# pwr_brk.net
KiCad netlist of a schematic drawn in Altium Designer
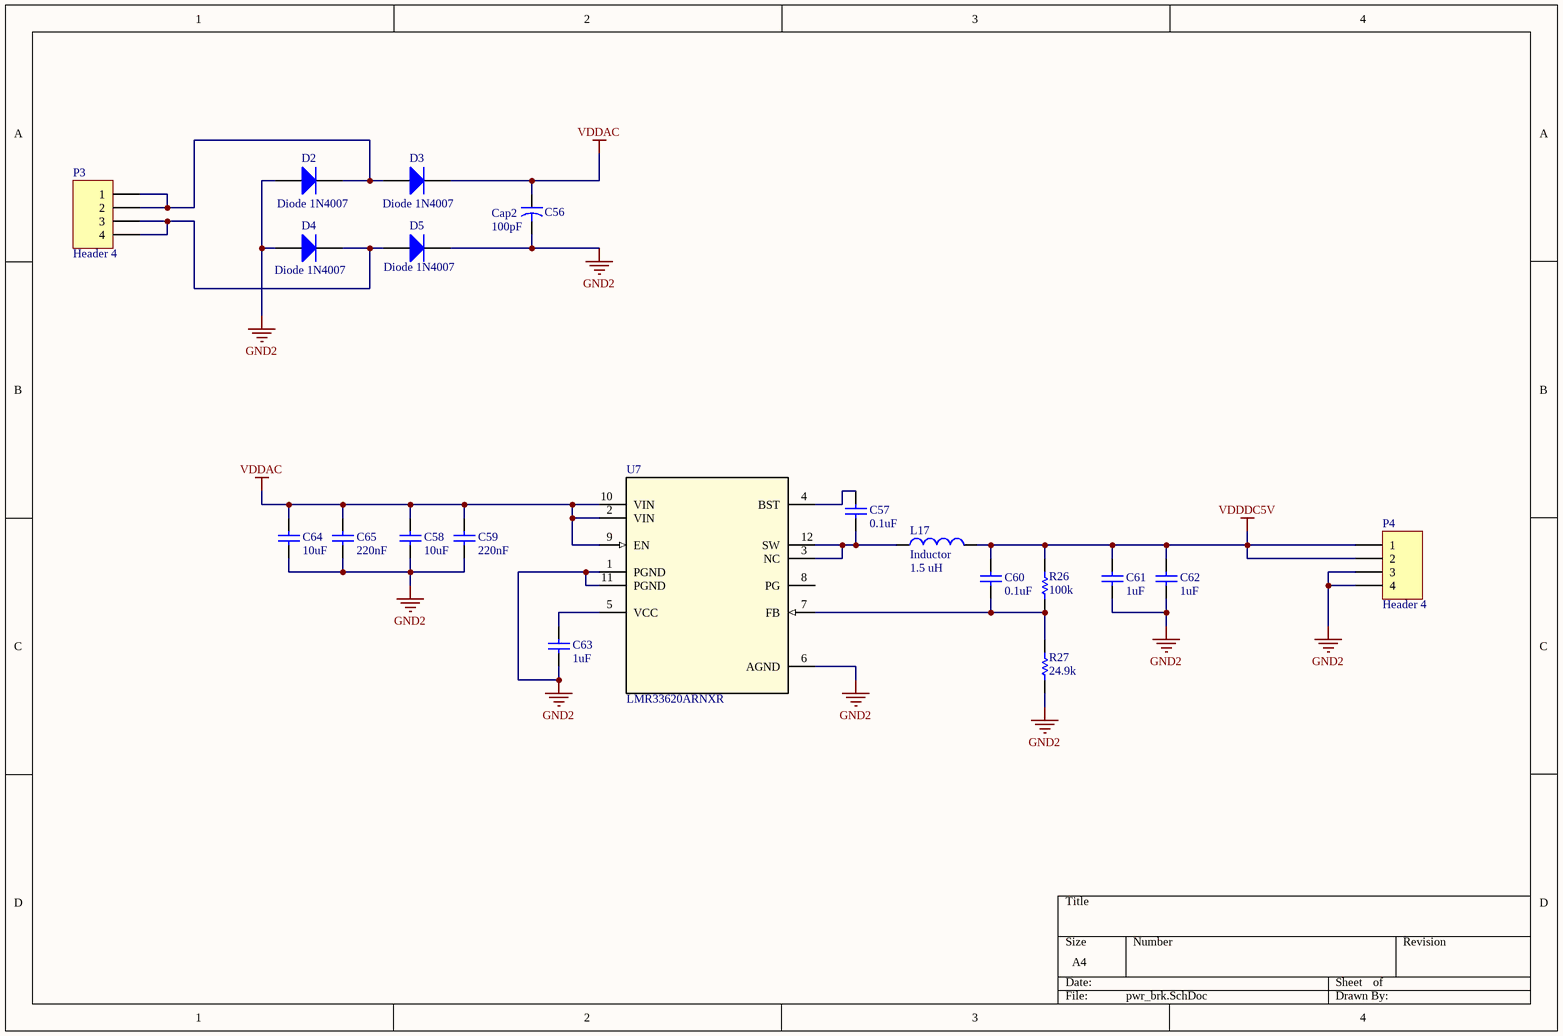
[diagram p0: pwr_brk.SchDoc]

(export (version "E")
  (design (tool "Eeschema 10.0.6"))
  (components
    (comp (ref "C56")
      (value "Cap2")
      (footprint "CAPR5-4X5")
      (description "Capacitor")
      (fields (field (name "ALTIUM_VALUE") "100pF") (field (name "PUBLISHER") "Altium Limited"))
      (libsource (lib "Miscellaneous Devices") (part "Cap2"))
    )
    (comp (ref "C57")
      (value "0.1uF")
      (footprint "C_0402")
      (libsource (lib "Miscellaneous Devices") (part "Cap"))
    )
    (comp (ref "C58")
      (value "10uF")
      (footprint "CAPC1608X05N")
      (libsource (lib "Miscellaneous Devices") (part "Cap"))
    )
    (comp (ref "C59")
      (value "220nF")
      (footprint "C_0402")
      (libsource (lib "Miscellaneous Devices") (part "Cap"))
    )
    (comp (ref "C60")
      (value "0.1uF")
      (footprint "C_0402")
      (libsource (lib "Miscellaneous Devices") (part "Cap"))
    )
    (comp (ref "C61")
      (value "1uF")
      (footprint "CAPC1608X05N")
      (libsource (lib "Miscellaneous Devices") (part "Cap"))
    )
    (comp (ref "C62")
      (value "1uF")
      (footprint "CAPC1608X05N")
      (libsource (lib "Miscellaneous Devices") (part "Cap"))
    )
    (comp (ref "C63")
      (value "1uF")
      (footprint "C_0402")
      (libsource (lib "Miscellaneous Devices") (part "Cap"))
    )
    (comp (ref "C64")
      (value "10uF")
      (footprint "CAPC1608X05N")
      (libsource (lib "Miscellaneous Devices") (part "Cap"))
    )
    (comp (ref "C65")
      (value "220nF")
      (footprint "C_0402")
      (libsource (lib "Miscellaneous Devices") (part "Cap"))
    )
    (comp (ref "D2")
      (value "Diode 1N4007")
      (footprint "DO-41")
      (description "1 Amp General Purpose Rectifier")
      (fields (field (name "PUBLISHER") "Altium Limited"))
      (libsource (lib "Miscellaneous Devices") (part "Diode 1N4007"))
    )
    (comp (ref "D3")
      (value "Diode 1N4007")
      (footprint "DO-41")
      (description "1 Amp General Purpose Rectifier")
      (fields (field (name "PUBLISHER") "Altium Limited"))
      (libsource (lib "Miscellaneous Devices") (part "Diode 1N4007"))
    )
    (comp (ref "D4")
      (value "Diode 1N4007")
      (footprint "DO-41")
      (description "1 Amp General Purpose Rectifier")
      (fields (field (name "PUBLISHER") "Altium Limited"))
      (libsource (lib "Miscellaneous Devices") (part "Diode 1N4007"))
    )
    (comp (ref "D5")
      (value "Diode 1N4007")
      (footprint "DO-41")
      (description "1 Amp General Purpose Rectifier")
      (fields (field (name "PUBLISHER") "Altium Limited"))
      (libsource (lib "Miscellaneous Devices") (part "Diode 1N4007"))
    )
    (comp (ref "L17")
      (value "Inductor")
      (footprint "INDC2016X10N")
      (fields (field (name "ALTIUM_VALUE") "1.5 uH") (field (name "PUBLISHER") "Altium Limited"))
      (libsource (lib "Miscellaneous Devices") (part "Inductor"))
    )
    (comp (ref "P3")
      (value "Header 4")
      (footprint "HDR1X4")
      (description "Header, 4-Pin")
      (fields (field (name "PUBLISHER") "Altium Limited"))
      (libsource (lib "Miscellaneous Connectors") (part "Header 4"))
    )
    (comp (ref "P4")
      (value "Header 4")
      (footprint "HDR1X4")
      (description "Header, 4-Pin")
      (fields (field (name "PUBLISHER") "Altium Limited"))
      (libsource (lib "") (part "Header 4_1"))
    )
    (comp (ref "R26")
      (value "Res1")
      (footprint "R_0402")
      (description "Resistor")
      (fields (field (name "ALTIUM_UNNAMED_1") "100k"))
      (libsource (lib "Miscellaneous Devices") (part "Res1"))
    )
    (comp (ref "R27")
      (value "Res1")
      (footprint "R_0402")
      (description "Resistor")
      (fields (field (name "ALTIUM_UNNAMED_1") "24.9k"))
      (libsource (lib "Miscellaneous Devices") (part "Res1"))
    )
    (comp (ref "U7")
      (value "LMR33620ARNXR")
      (footprint "RNX0012B")
      (description "Imported")
      (fields (field (name "MANUFACTURER") "Texas Instruments"))
      (libsource (lib "LMR33620") (part "LMR33620ARNXR"))
    )
  )
  (nets
    (net (code "1") (name "GND2") (class "Default")
      (node (ref "C56") (pin "2") (pinfunction "2_2") (pintype "passive"))
      (node (ref "C58") (pin "1") (pinfunction "1_1") (pintype "passive"))
      (node (ref "C59") (pin "1") (pinfunction "1_1") (pintype "passive"))
      (node (ref "C61") (pin "1") (pinfunction "1_1") (pintype "passive"))
      (node (ref "C62") (pin "1") (pinfunction "1_1") (pintype "passive"))
      (node (ref "C63") (pin "1") (pinfunction "1_1") (pintype "passive"))
      (node (ref "C64") (pin "1") (pinfunction "1_1") (pintype "passive"))
      (node (ref "C65") (pin "1") (pinfunction "1_1") (pintype "passive"))
      (node (ref "D2") (pin "1") (pinfunction "A_1") (pintype "passive"))
      (node (ref "D4") (pin "1") (pinfunction "A_1") (pintype "passive"))
      (node (ref "D5") (pin "2") (pinfunction "K_2") (pintype "passive"))
      (node (ref "P4") (pin "3") (pinfunction "3_3") (pintype "passive"))
      (node (ref "P4") (pin "4") (pinfunction "4_4") (pintype "passive"))
      (node (ref "R27") (pin "2") (pinfunction "2_2") (pintype "passive"))
      (node (ref "U7") (pin "1") (pinfunction "PGND_1") (pintype "power_in"))
      (node (ref "U7") (pin "11") (pinfunction "PGND_11") (pintype "power_in"))
      (node (ref "U7") (pin "6") (pinfunction "AGND_6") (pintype "power_in"))
    )
    (net (code "2") (name "Net-(D2-K)") (class "Default")
      (node (ref "D2") (pin "2") (pinfunction "K_2") (pintype "passive"))
      (node (ref "D3") (pin "1") (pinfunction "A_1") (pintype "passive"))
      (node (ref "P3") (pin "1") (pinfunction "1_1") (pintype "passive"))
      (node (ref "P3") (pin "2") (pinfunction "2_2") (pintype "passive"))
    )
    (net (code "3") (name "Net-(D4-K)") (class "Default")
      (node (ref "D4") (pin "2") (pinfunction "K_2") (pintype "passive"))
      (node (ref "D5") (pin "1") (pinfunction "A_1") (pintype "passive"))
      (node (ref "P3") (pin "3") (pinfunction "3_3") (pintype "passive"))
      (node (ref "P3") (pin "4") (pinfunction "4_4") (pintype "passive"))
    )
    (net (code "4") (name "Net-(U7-BST)") (class "Default")
      (node (ref "C57") (pin "2") (pinfunction "2_2") (pintype "passive"))
      (node (ref "U7") (pin "4") (pinfunction "BST_4") (pintype "passive"))
    )
    (net (code "5") (name "Net-(U7-FB)") (class "Default")
      (node (ref "C60") (pin "1") (pinfunction "1_1") (pintype "passive"))
      (node (ref "R26") (pin "2") (pinfunction "2_2") (pintype "passive"))
      (node (ref "R27") (pin "1") (pinfunction "1_1") (pintype "passive"))
      (node (ref "U7") (pin "7") (pinfunction "FB_7") (pintype "input"))
    )
    (net (code "6") (name "Net-(U7-NC)") (class "Default")
      (node (ref "C57") (pin "1") (pinfunction "1_1") (pintype "passive"))
      (node (ref "L17") (pin "1") (pinfunction "1_1") (pintype "passive"))
      (node (ref "U7") (pin "12") (pinfunction "SW_12") (pintype "power_in"))
      (node (ref "U7") (pin "3") (pinfunction "NC_3") (pintype "passive"))
    )
    (net (code "7") (name "Net-(U7-VCC)") (class "Default")
      (node (ref "C63") (pin "2") (pinfunction "2_2") (pintype "passive"))
      (node (ref "U7") (pin "5") (pinfunction "VCC_5") (pintype "power_in"))
    )
    (net (code "8") (name "VDDAC") (class "Default")
      (node (ref "C56") (pin "1") (pinfunction "1_1") (pintype "passive"))
      (node (ref "C58") (pin "2") (pinfunction "2_2") (pintype "passive"))
      (node (ref "C59") (pin "2") (pinfunction "2_2") (pintype "passive"))
      (node (ref "C64") (pin "2") (pinfunction "2_2") (pintype "passive"))
      (node (ref "C65") (pin "2") (pinfunction "2_2") (pintype "passive"))
      (node (ref "D3") (pin "2") (pinfunction "K_2") (pintype "passive"))
      (node (ref "U7") (pin "10") (pinfunction "VIN_10") (pintype "power_in"))
      (node (ref "U7") (pin "2") (pinfunction "VIN_2") (pintype "power_in"))
      (node (ref "U7") (pin "9") (pinfunction "EN_9") (pintype "input"))
    )
    (net (code "9") (name "VDDDC5V") (class "Default")
      (node (ref "C60") (pin "2") (pinfunction "2_2") (pintype "passive"))
      (node (ref "C61") (pin "2") (pinfunction "2_2") (pintype "passive"))
      (node (ref "C62") (pin "2") (pinfunction "2_2") (pintype "passive"))
      (node (ref "L17") (pin "2") (pinfunction "2_2") (pintype "passive"))
      (node (ref "P4") (pin "1") (pinfunction "1_1") (pintype "passive"))
      (node (ref "P4") (pin "2") (pinfunction "2_2") (pintype "passive"))
      (node (ref "R26") (pin "1") (pinfunction "1_1") (pintype "passive"))
    )
    (net (code "10") (name "unconnected-(U7-PG-Pad8)") (class "Default")
      (node (ref "U7") (pin "8") (pinfunction "PG_8") (pintype "open_collector"))
    )
  )
)
